# controller.net
KiCad netlist of a schematic drawn in EAGLE
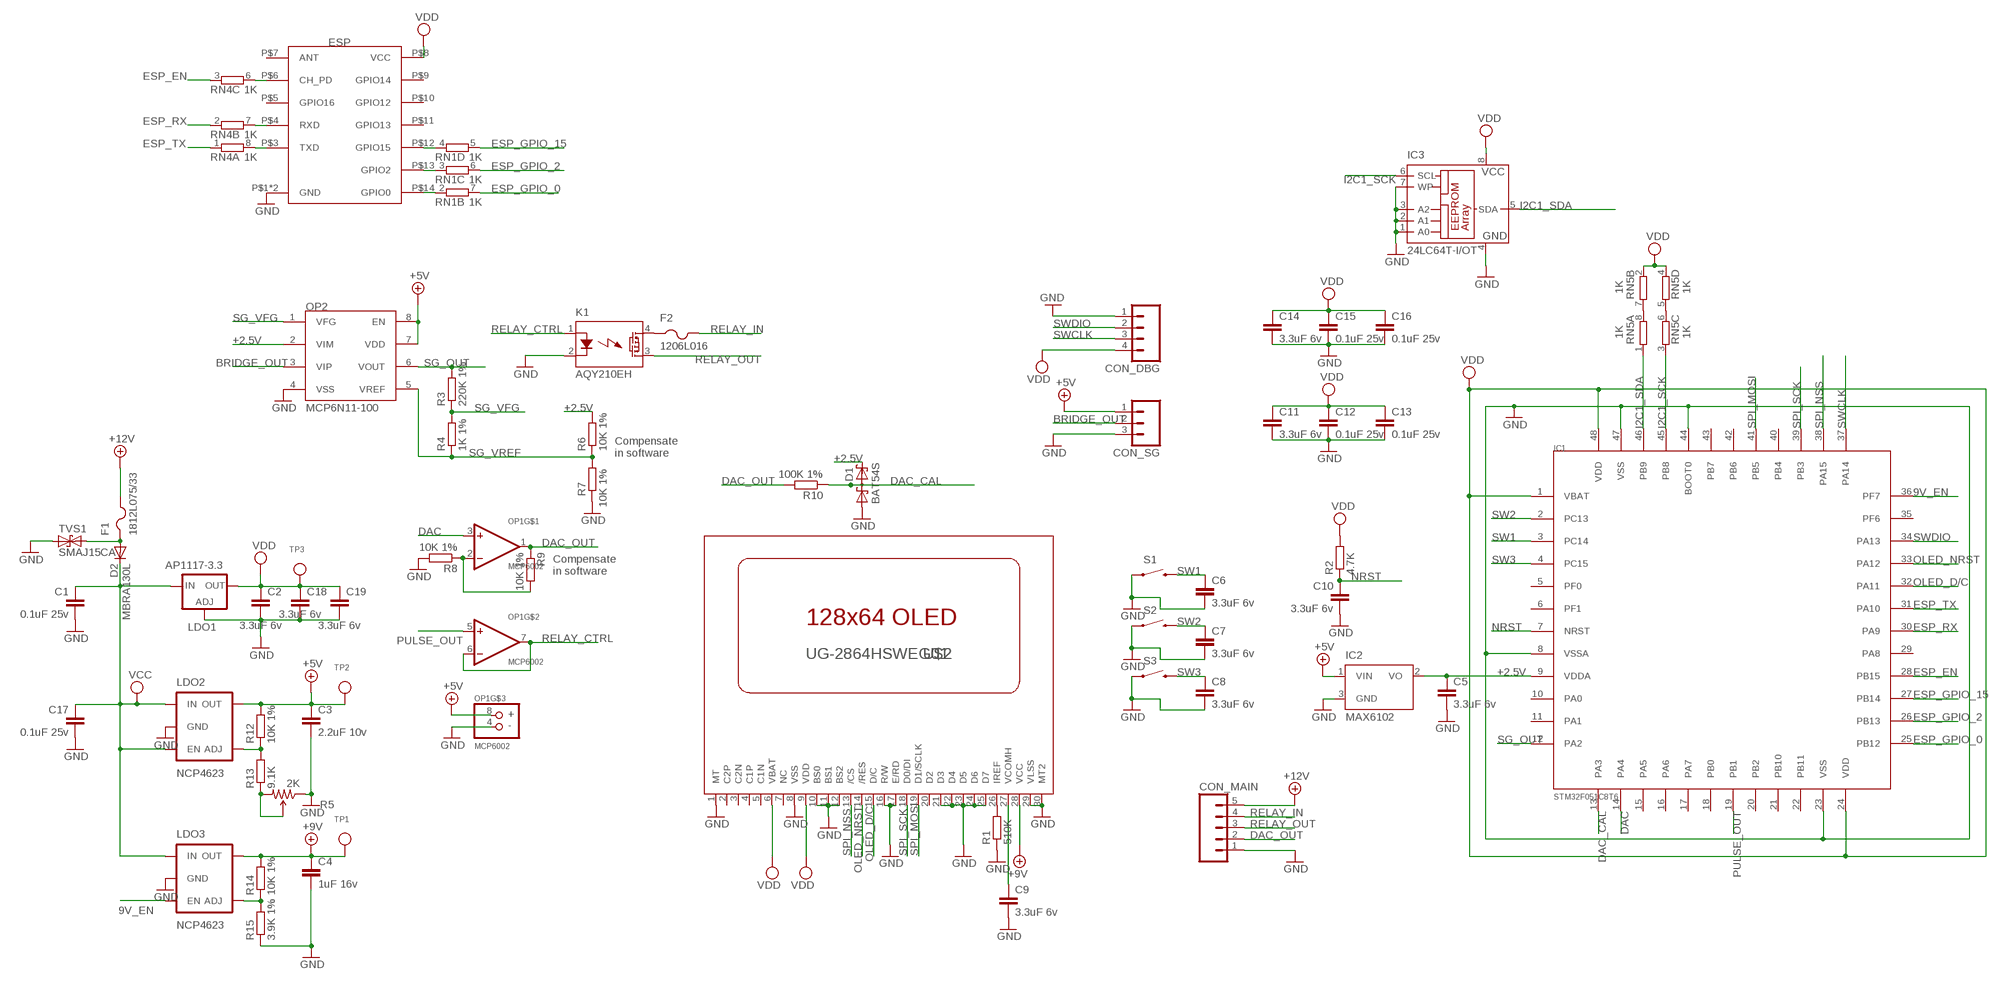
[diagram p0: schematic, sheet 1]

(export (version "E")
  (design (tool "Eeschema 10.0.6"))
  (components
    (comp (ref "C1")
      (value "0.1uF 25v")
      (footprint "eagle-import:C0603")
      (libsource (lib "eagle-import") (part "C-EUC0603"))
    )
    (comp (ref "C2")
      (value "3.3uF 6v")
      (footprint "eagle-import:C0603")
      (libsource (lib "eagle-import") (part "C-EUC0603"))
    )
    (comp (ref "C3")
      (value "2.2uF 10v")
      (footprint "eagle-import:C0603")
      (libsource (lib "eagle-import") (part "C-EUC0603"))
    )
    (comp (ref "C4")
      (value "1uF 16v")
      (footprint "eagle-import:C0603")
      (libsource (lib "eagle-import") (part "C-EUC0603"))
    )
    (comp (ref "C5")
      (value "3.3uF 6v")
      (footprint "eagle-import:C0603")
      (libsource (lib "eagle-import") (part "C-EUC0603"))
    )
    (comp (ref "C6")
      (value "3.3uF 6v")
      (footprint "eagle-import:C0603")
      (libsource (lib "eagle-import") (part "C-EUC0603"))
    )
    (comp (ref "C7")
      (value "3.3uF 6v")
      (footprint "eagle-import:C0603")
      (libsource (lib "eagle-import") (part "C-EUC0603"))
    )
    (comp (ref "C8")
      (value "3.3uF 6v")
      (footprint "eagle-import:C0603")
      (libsource (lib "eagle-import") (part "C-EUC0603"))
    )
    (comp (ref "C9")
      (value "3.3uF 6v")
      (footprint "eagle-import:C0603")
      (libsource (lib "eagle-import") (part "C-EUC0603"))
    )
    (comp (ref "C10")
      (value "3.3uF 6v")
      (footprint "eagle-import:C0603")
      (libsource (lib "eagle-import") (part "C-EUC0603"))
    )
    (comp (ref "C11")
      (value "3.3uF 6v")
      (footprint "eagle-import:C0603")
      (libsource (lib "eagle-import") (part "C-EUC0603"))
    )
    (comp (ref "C12")
      (value "0.1uF 25v")
      (footprint "eagle-import:C0603")
      (libsource (lib "eagle-import") (part "C-EUC0603"))
    )
    (comp (ref "C13")
      (value "0.1uF 25v")
      (footprint "eagle-import:C0603")
      (libsource (lib "eagle-import") (part "C-EUC0603"))
    )
    (comp (ref "C14")
      (value "3.3uF 6v")
      (footprint "eagle-import:C0603")
      (libsource (lib "eagle-import") (part "C-EUC0603"))
    )
    (comp (ref "C15")
      (value "0.1uF 25v")
      (footprint "eagle-import:C0603")
      (libsource (lib "eagle-import") (part "C-EUC0603"))
    )
    (comp (ref "C16")
      (value "0.1uF 25v")
      (footprint "eagle-import:C0603")
      (libsource (lib "eagle-import") (part "C-EUC0603"))
    )
    (comp (ref "C17")
      (value "0.1uF 25v")
      (footprint "eagle-import:C0603")
      (libsource (lib "eagle-import") (part "C-EUC0603"))
    )
    (comp (ref "C18")
      (value "3.3uF 6v")
      (footprint "eagle-import:C0603")
      (libsource (lib "eagle-import") (part "C-EUC0603"))
    )
    (comp (ref "C19")
      (value "3.3uF 6v")
      (footprint "eagle-import:C0603")
      (libsource (lib "eagle-import") (part "C-EUC0603"))
    )
    (comp (ref "CON_DBG")
      (value "M04LOCK")
      (footprint "eagle-import:1X04_LOCK")
      (libsource (lib "eagle-import") (part "M04LOCK"))
    )
    (comp (ref "CON_MAIN")
      (value "M05LOCK")
      (footprint "eagle-import:1X05_LOCK")
      (libsource (lib "eagle-import") (part "M05LOCK"))
    )
    (comp (ref "CON_SG")
      (value "M03LOCK")
      (footprint "eagle-import:1X03_LOCK")
      (libsource (lib "eagle-import") (part "M03LOCK"))
    )
    (comp (ref "D1")
      (value "BAT54S")
      (footprint "eagle-import:SOT23")
      (libsource (lib "eagle-import") (part "BAT54S"))
    )
    (comp (ref "D2")
      (value "MBRA130L")
      (footprint "eagle-import:SMA-DIODE")
      (libsource (lib "eagle-import") (part "DIODESMA"))
    )
    (comp (ref "ESP")
      (value "ESP8266")
      (footprint "eagle-import:ESP-03")
      (libsource (lib "eagle-import") (part "ESP8266"))
    )
    (comp (ref "F1")
      (value "1812L075/33")
      (footprint "eagle-import:1812")
      (libsource (lib "eagle-import") (part "PTCFUSE-1812"))
    )
    (comp (ref "F2")
      (value "1206L016")
      (footprint "eagle-import:R1206")
      (libsource (lib "eagle-import") (part "PTCFUSE-1206"))
    )
    (comp (ref "IC1")
      (value "STM32F051C8T6")
      (footprint "eagle-import:LQFP-48")
      (libsource (lib "eagle-import") (part "STM32F05XC"))
    )
    (comp (ref "IC2")
      (value "MAX6102")
      (footprint "eagle-import:SOT23")
      (libsource (lib "eagle-import") (part "MC15TT25"))
    )
    (comp (ref "IC3")
      (value "24LC64T-I/OT")
      (footprint "eagle-import:SO-08")
      (fields (field (name "MPN") "AT24C01BN-SH-B"))
      (libsource (lib "eagle-import") (part "24CSN01A"))
    )
    (comp (ref "K1")
      (value "AQY210EH")
      (footprint "eagle-import:SOP04")
      (libsource (lib "eagle-import") (part "AQYSOP21"))
    )
    (comp (ref "LDO1")
      (value "AP1117-3.3")
      (footprint "eagle-import:DPACK")
      (libsource (lib "eagle-import") (part "LD117A?DT33TR"))
    )
    (comp (ref "LDO2")
      (value "NCP4623")
      (footprint "eagle-import:SOT23-5")
      (libsource (lib "eagle-import") (part "NCP4623"))
    )
    (comp (ref "LDO3")
      (value "NCP4623")
      (footprint "eagle-import:SOT23-5")
      (libsource (lib "eagle-import") (part "NCP4623"))
    )
    (comp (ref "OP1")
      (value "MCP6002")
      (footprint "eagle-import:MSOP-8")
      (libsource (lib "eagle-import") (part "MCP6022-MSOP"))
    )
    (comp (ref "OP2")
      (value "MCP6N11-100")
      (footprint "eagle-import:SO08")
      (libsource (lib "eagle-import") (part "MCP6N11"))
    )
    (comp (ref "R1")
      (value "510K")
      (footprint "eagle-import:R0603")
      (libsource (lib "eagle-import") (part "R-EU_R0603"))
    )
    (comp (ref "R2")
      (value "4.7K")
      (footprint "eagle-import:R0603")
      (libsource (lib "eagle-import") (part "R-EU_R0603"))
    )
    (comp (ref "R3")
      (value "220K 1%")
      (footprint "eagle-import:R0603")
      (libsource (lib "eagle-import") (part "R-EU_R0603"))
    )
    (comp (ref "R4")
      (value "1K 1%")
      (footprint "eagle-import:R0603")
      (libsource (lib "eagle-import") (part "R-EU_R0603"))
    )
    (comp (ref "R5")
      (value "2K")
      (footprint "eagle-import:TRIMPOT-3MM-2")
      (libsource (lib "eagle-import") (part "TRIMPOT3MM-2"))
    )
    (comp (ref "R6")
      (value "10K 1%")
      (footprint "eagle-import:R0603")
      (libsource (lib "eagle-import") (part "R-EU_R0603"))
    )
    (comp (ref "R7")
      (value "10K 1%")
      (footprint "eagle-import:R0603")
      (libsource (lib "eagle-import") (part "R-EU_R0603"))
    )
    (comp (ref "R8")
      (value "10K 1%")
      (footprint "eagle-import:R0603")
      (libsource (lib "eagle-import") (part "R-EU_R0603"))
    )
    (comp (ref "R9")
      (value "10K 1%")
      (footprint "eagle-import:R0603")
      (libsource (lib "eagle-import") (part "R-EU_R0603"))
    )
    (comp (ref "R10")
      (value "100K 1%")
      (footprint "eagle-import:R0603")
      (libsource (lib "eagle-import") (part "R-EU_R0603"))
    )
    (comp (ref "R12")
      (value "10K 1%")
      (footprint "eagle-import:R0603")
      (libsource (lib "eagle-import") (part "R-EU_R0603"))
    )
    (comp (ref "R13")
      (value "9.1K")
      (footprint "eagle-import:R0603")
      (libsource (lib "eagle-import") (part "R-EU_R0603"))
    )
    (comp (ref "R14")
      (value "10K 1%")
      (footprint "eagle-import:R0603")
      (libsource (lib "eagle-import") (part "R-EU_R0603"))
    )
    (comp (ref "R15")
      (value "3.9K 1%")
      (footprint "eagle-import:R0603")
      (libsource (lib "eagle-import") (part "R-EU_R0603"))
    )
    (comp (ref "RN1")
      (value "1K")
      (footprint "eagle-import:CAY16")
      (libsource (lib "eagle-import") (part "4R-NCAY16"))
    )
    (comp (ref "RN4")
      (value "1K")
      (footprint "eagle-import:CAY16")
      (libsource (lib "eagle-import") (part "4R-NCAY16"))
    )
    (comp (ref "RN5")
      (value "1K")
      (footprint "eagle-import:CAY16")
      (libsource (lib "eagle-import") (part "4R-NCAY16"))
    )
    (comp (ref "S1")
      (value "SWITCH-MOMENTARY-2SMD-2")
      (footprint "eagle-import:TACTILE_SWITCH_SMD-2")
      (libsource (lib "eagle-import") (part "SWITCH-MOMENTARY-2SMD-2"))
    )
    (comp (ref "S2")
      (value "SWITCH-MOMENTARY-2SMD-2")
      (footprint "eagle-import:TACTILE_SWITCH_SMD-2")
      (libsource (lib "eagle-import") (part "SWITCH-MOMENTARY-2SMD-2"))
    )
    (comp (ref "S3")
      (value "SWITCH-MOMENTARY-2SMD-2")
      (footprint "eagle-import:TACTILE_SWITCH_SMD-2")
      (libsource (lib "eagle-import") (part "SWITCH-MOMENTARY-2SMD-2"))
    )
    (comp (ref "TP1")
      (value "TESTPOINTROUND2MM")
      (footprint "eagle-import:TESTPOINT_ROUND_2MM")
      (libsource (lib "eagle-import") (part "TESTPOINTROUND2MM"))
    )
    (comp (ref "TP2")
      (value "TESTPOINTROUND2MM")
      (footprint "eagle-import:TESTPOINT_ROUND_2MM")
      (libsource (lib "eagle-import") (part "TESTPOINTROUND2MM"))
    )
    (comp (ref "TP3")
      (value "TESTPOINTROUND2MM")
      (footprint "eagle-import:TESTPOINT_ROUND_2MM")
      (libsource (lib "eagle-import") (part "TESTPOINTROUND2MM"))
    )
    (comp (ref "TVS1")
      (value "SMAJ15CA")
      (footprint "eagle-import:SMA-DIODE")
      (libsource (lib "eagle-import") (part "TVS"))
    )
    (comp (ref "U$2")
      (value "UG-2864HSWEG01")
      (footprint "eagle-import:1X30-0.7MM")
      (libsource (lib "eagle-import") (part "UG-2864HSWEG01"))
    )
  )
  (nets
    (net (code "1") (name "+5V") (class "Default")
      (node (ref "C3") (pin "1") (pinfunction "1_1") (pintype "passive"))
      (node (ref "CON_SG") (pin "1") (pinfunction "1_1") (pintype "passive"))
      (node (ref "IC2") (pin "1") (pinfunction "VIN_1") (pintype "input"))
      (node (ref "LDO2") (pin "1") (pinfunction "OUT_1") (pintype "passive"))
      (node (ref "OP1") (pin "8") (pinfunction "+_8") (pintype "passive"))
      (node (ref "OP2") (pin "7") (pinfunction "VDD_7") (pintype "bidirectional"))
      (node (ref "OP2") (pin "8") (pinfunction "EN_8") (pintype "bidirectional"))
      (node (ref "R12") (pin "2") (pinfunction "2_2") (pintype "passive"))
      (node (ref "TP2") (pin "P$1") (pinfunction "P$1_P$1") (pintype "bidirectional"))
    )
    (net (code "2") (name "+9V") (class "Default")
      (node (ref "C4") (pin "1") (pinfunction "1_1") (pintype "passive"))
      (node (ref "LDO3") (pin "1") (pinfunction "OUT_1") (pintype "passive"))
      (node (ref "R14") (pin "2") (pinfunction "2_2") (pintype "passive"))
      (node (ref "TP1") (pin "P$1") (pinfunction "P$1_P$1") (pintype "bidirectional"))
      (node (ref "U$2") (pin "28") (pinfunction "VCC_28") (pintype "power_in"))
    )
    (net (code "3") (name "+12V") (class "Default")
      (node (ref "CON_MAIN") (pin "5") (pinfunction "5_5") (pintype "passive"))
      (node (ref "F1") (pin "2") (pinfunction "2_2") (pintype "passive"))
    )
    (net (code "4") (name "/+2.5V") (class "Default")
      (node (ref "C5") (pin "1") (pinfunction "1_1") (pintype "passive"))
      (node (ref "D1") (pin "2") (pinfunction "C2_2") (pintype "passive"))
      (node (ref "IC1") (pin "9") (pinfunction "VDDA_9") (pintype "bidirectional"))
      (node (ref "IC2") (pin "2") (pinfunction "VO_2") (pintype "output"))
      (node (ref "OP2") (pin "2") (pinfunction "VIM_2") (pintype "bidirectional"))
      (node (ref "R6") (pin "2") (pinfunction "2_2") (pintype "passive"))
    )
    (net (code "5") (name "/9V_EN") (class "Default")
      (node (ref "IC1") (pin "36") (pinfunction "PF7_36") (pintype "bidirectional"))
      (node (ref "LDO3") (pin "5") (pinfunction "EN_5") (pintype "input"))
    )
    (net (code "6") (name "/BRIDGE_OUT") (class "Default")
      (node (ref "CON_SG") (pin "2") (pinfunction "2_2") (pintype "passive"))
      (node (ref "OP2") (pin "3") (pinfunction "VIP_3") (pintype "bidirectional"))
    )
    (net (code "7") (name "/DAC") (class "Default")
      (node (ref "IC1") (pin "14") (pinfunction "PA4_14") (pintype "bidirectional"))
      (node (ref "OP1") (pin "3") (pinfunction "+IN_3") (pintype "input"))
    )
    (net (code "8") (name "/DAC_CAL") (class "Default")
      (node (ref "D1") (pin "3") (pinfunction "C1A2_3") (pintype "passive"))
      (node (ref "IC1") (pin "13") (pinfunction "PA3_13") (pintype "bidirectional"))
      (node (ref "R10") (pin "1") (pinfunction "1_1") (pintype "passive"))
    )
    (net (code "9") (name "/DAC_OUT") (class "Default")
      (node (ref "CON_MAIN") (pin "2") (pinfunction "2_2") (pintype "passive"))
      (node (ref "OP1") (pin "1") (pinfunction "OUT_1") (pintype "output"))
      (node (ref "R10") (pin "2") (pinfunction "2_2") (pintype "passive"))
      (node (ref "R9") (pin "1") (pinfunction "1_1") (pintype "passive"))
    )
    (net (code "10") (name "/ESP_EN") (class "Default")
      (node (ref "IC1") (pin "28") (pinfunction "PB15_28") (pintype "bidirectional"))
      (node (ref "RN4") (pin "3") (pinfunction "1_3") (pintype "passive"))
    )
    (net (code "11") (name "/ESP_GPIO_0") (class "Default")
      (node (ref "IC1") (pin "25") (pinfunction "PB12_25") (pintype "bidirectional"))
      (node (ref "RN1") (pin "7") (pinfunction "2_7") (pintype "passive"))
    )
    (net (code "12") (name "/ESP_GPIO_2") (class "Default")
      (node (ref "IC1") (pin "26") (pinfunction "PB13_26") (pintype "bidirectional"))
      (node (ref "RN1") (pin "6") (pinfunction "2_6") (pintype "passive"))
    )
    (net (code "13") (name "/ESP_GPIO_15") (class "Default")
      (node (ref "IC1") (pin "27") (pinfunction "PB14_27") (pintype "bidirectional"))
      (node (ref "RN1") (pin "5") (pinfunction "2_5") (pintype "passive"))
    )
    (net (code "14") (name "/ESP_RX") (class "Default")
      (node (ref "IC1") (pin "30") (pinfunction "PA9_30") (pintype "bidirectional"))
      (node (ref "RN4") (pin "2") (pinfunction "1_2") (pintype "passive"))
    )
    (net (code "15") (name "/ESP_TX") (class "Default")
      (node (ref "IC1") (pin "31") (pinfunction "PA10_31") (pintype "bidirectional"))
      (node (ref "RN4") (pin "1") (pinfunction "1_1") (pintype "passive"))
    )
    (net (code "16") (name "/I2C1_SCK") (class "Default")
      (node (ref "IC1") (pin "45") (pinfunction "PB8_45") (pintype "bidirectional"))
      (node (ref "IC3") (pin "6") (pinfunction "SCL_6") (pintype "input"))
      (node (ref "RN5") (pin "3") (pinfunction "1_3") (pintype "passive"))
    )
    (net (code "17") (name "/I2C1_SDA") (class "Default")
      (node (ref "IC1") (pin "46") (pinfunction "PB9_46") (pintype "bidirectional"))
      (node (ref "IC3") (pin "5") (pinfunction "SDA_5") (pintype "bidirectional"))
      (node (ref "RN5") (pin "1") (pinfunction "1_1") (pintype "passive"))
    )
    (net (code "18") (name "/NRST") (class "Default")
      (node (ref "C10") (pin "1") (pinfunction "1_1") (pintype "passive"))
      (node (ref "IC1") (pin "7") (pinfunction "NRST_7") (pintype "bidirectional"))
      (node (ref "R2") (pin "1") (pinfunction "1_1") (pintype "passive"))
    )
    (net (code "19") (name "/OLED_D{slash}C") (class "Default")
      (node (ref "IC1") (pin "32") (pinfunction "PA11_32") (pintype "bidirectional"))
      (node (ref "U$2") (pin "15") (pinfunction "D/C_15") (pintype "input"))
    )
    (net (code "20") (name "/OLED_NRST") (class "Default")
      (node (ref "IC1") (pin "33") (pinfunction "PA12_33") (pintype "bidirectional"))
      (node (ref "U$2") (pin "14") (pinfunction "/RES_14") (pintype "input"))
    )
    (net (code "21") (name "/PULSE_OUT") (class "Default")
      (node (ref "IC1") (pin "19") (pinfunction "PB1_19") (pintype "bidirectional"))
      (node (ref "OP1") (pin "5") (pinfunction "+IN_5") (pintype "input"))
    )
    (net (code "22") (name "/RELAY_CTRL") (class "Default")
      (node (ref "K1") (pin "1") (pinfunction "A_1") (pintype "passive"))
      (node (ref "OP1") (pin "6") (pinfunction "-IN_6") (pintype "input"))
      (node (ref "OP1") (pin "7") (pinfunction "OUT_7") (pintype "output"))
    )
    (net (code "23") (name "/RELAY_IN") (class "Default")
      (node (ref "CON_MAIN") (pin "4") (pinfunction "4_4") (pintype "passive"))
      (node (ref "F2") (pin "2") (pinfunction "2_2") (pintype "passive"))
    )
    (net (code "24") (name "/RELAY_OUT") (class "Default")
      (node (ref "CON_MAIN") (pin "3") (pinfunction "3_3") (pintype "passive"))
      (node (ref "K1") (pin "3") (pinfunction "DS2_3") (pintype "passive"))
    )
    (net (code "25") (name "/SG_OUT") (class "Default")
      (node (ref "IC1") (pin "12") (pinfunction "PA2_12") (pintype "bidirectional"))
      (node (ref "OP2") (pin "6") (pinfunction "VOUT_6") (pintype "bidirectional"))
      (node (ref "R3") (pin "2") (pinfunction "2_2") (pintype "passive"))
    )
    (net (code "26") (name "/SG_VFG") (class "Default")
      (node (ref "OP2") (pin "1") (pinfunction "VFG_1") (pintype "bidirectional"))
      (node (ref "R3") (pin "1") (pinfunction "1_1") (pintype "passive"))
      (node (ref "R4") (pin "2") (pinfunction "2_2") (pintype "passive"))
    )
    (net (code "27") (name "/SG_VREF") (class "Default")
      (node (ref "OP2") (pin "5") (pinfunction "VREF_5") (pintype "bidirectional"))
      (node (ref "R4") (pin "1") (pinfunction "1_1") (pintype "passive"))
      (node (ref "R6") (pin "1") (pinfunction "1_1") (pintype "passive"))
      (node (ref "R7") (pin "2") (pinfunction "2_2") (pintype "passive"))
    )
    (net (code "28") (name "/SPI_MOSI") (class "Default")
      (node (ref "IC1") (pin "41") (pinfunction "PB5_41") (pintype "bidirectional"))
      (node (ref "U$2") (pin "19") (pinfunction "D1/SCLK_19") (pintype "bidirectional"))
    )
    (net (code "29") (name "/SPI_NSS") (class "Default")
      (node (ref "IC1") (pin "38") (pinfunction "PA15_38") (pintype "bidirectional"))
      (node (ref "U$2") (pin "13") (pinfunction "/CS_13") (pintype "input"))
    )
    (net (code "30") (name "/SPI_SCK") (class "Default")
      (node (ref "IC1") (pin "39") (pinfunction "PB3_39") (pintype "bidirectional"))
      (node (ref "U$2") (pin "18") (pinfunction "D0/DI_18") (pintype "bidirectional"))
    )
    (net (code "31") (name "/SW1") (class "Default")
      (node (ref "C6") (pin "1") (pinfunction "1_1") (pintype "passive"))
      (node (ref "IC1") (pin "3") (pinfunction "PC14_3") (pintype "bidirectional"))
      (node (ref "S1") (pin "1") (pinfunction "2_1") (pintype "passive"))
    )
    (net (code "32") (name "/SW2") (class "Default")
      (node (ref "C7") (pin "1") (pinfunction "1_1") (pintype "passive"))
      (node (ref "IC1") (pin "2") (pinfunction "PC13_2") (pintype "bidirectional"))
      (node (ref "S2") (pin "1") (pinfunction "2_1") (pintype "passive"))
    )
    (net (code "33") (name "/SW3") (class "Default")
      (node (ref "C8") (pin "1") (pinfunction "1_1") (pintype "passive"))
      (node (ref "IC1") (pin "4") (pinfunction "PC15_4") (pintype "bidirectional"))
      (node (ref "S3") (pin "1") (pinfunction "2_1") (pintype "passive"))
    )
    (net (code "34") (name "/SWCLK") (class "Default")
      (node (ref "CON_DBG") (pin "3") (pinfunction "3_3") (pintype "passive"))
      (node (ref "IC1") (pin "37") (pinfunction "PA14_37") (pintype "bidirectional"))
    )
    (net (code "35") (name "/SWDIO") (class "Default")
      (node (ref "CON_DBG") (pin "2") (pinfunction "2_2") (pintype "passive"))
      (node (ref "IC1") (pin "34") (pinfunction "PA13_34") (pintype "bidirectional"))
    )
    (net (code "36") (name "GND") (class "Default")
      (node (ref "C1") (pin "2") (pinfunction "2_2") (pintype "passive"))
      (node (ref "C10") (pin "2") (pinfunction "2_2") (pintype "passive"))
      (node (ref "C11") (pin "2") (pinfunction "2_2") (pintype "passive"))
      (node (ref "C12") (pin "2") (pinfunction "2_2") (pintype "passive"))
      (node (ref "C13") (pin "2") (pinfunction "2_2") (pintype "passive"))
      (node (ref "C14") (pin "2") (pinfunction "2_2") (pintype "passive"))
      (node (ref "C15") (pin "2") (pinfunction "2_2") (pintype "passive"))
      (node (ref "C16") (pin "2") (pinfunction "2_2") (pintype "passive"))
      (node (ref "C17") (pin "2") (pinfunction "2_2") (pintype "passive"))
      (node (ref "C18") (pin "2") (pinfunction "2_2") (pintype "passive"))
      (node (ref "C19") (pin "2") (pinfunction "2_2") (pintype "passive"))
      (node (ref "C2") (pin "2") (pinfunction "2_2") (pintype "passive"))
      (node (ref "C3") (pin "2") (pinfunction "2_2") (pintype "passive"))
      (node (ref "C4") (pin "2") (pinfunction "2_2") (pintype "passive"))
      (node (ref "C5") (pin "2") (pinfunction "2_2") (pintype "passive"))
      (node (ref "C6") (pin "2") (pinfunction "2_2") (pintype "passive"))
      (node (ref "C7") (pin "2") (pinfunction "2_2") (pintype "passive"))
      (node (ref "C8") (pin "2") (pinfunction "2_2") (pintype "passive"))
      (node (ref "C9") (pin "2") (pinfunction "2_2") (pintype "passive"))
      (node (ref "CON_DBG") (pin "1") (pinfunction "1_1") (pintype "passive"))
      (node (ref "CON_MAIN") (pin "1") (pinfunction "1_1") (pintype "passive"))
      (node (ref "CON_SG") (pin "3") (pinfunction "3_3") (pintype "passive"))
      (node (ref "D1") (pin "1") (pinfunction "A1_1") (pintype "passive"))
      (node (ref "ESP") (pin "P$1") (pinfunction "GND_P$1") (pintype "bidirectional"))
      (node (ref "ESP") (pin "P$2") (pinfunction "GND_P$2") (pintype "bidirectional"))
      (node (ref "IC1") (pin "23") (pinfunction "VSS_23") (pintype "bidirectional"))
      (node (ref "IC1") (pin "44") (pinfunction "BOOT0_44") (pintype "bidirectional"))
      (node (ref "IC1") (pin "47") (pinfunction "VSS_47") (pintype "bidirectional"))
      (node (ref "IC1") (pin "8") (pinfunction "VSSA_8") (pintype "bidirectional"))
      (node (ref "IC2") (pin "3") (pinfunction "GND_3") (pintype "passive"))
      (node (ref "IC3") (pin "1") (pinfunction "A0_1") (pintype "input"))
      (node (ref "IC3") (pin "2") (pinfunction "A1_2") (pintype "input"))
      (node (ref "IC3") (pin "3") (pinfunction "A2_3") (pintype "input"))
      (node (ref "IC3") (pin "4") (pinfunction "GND_4") (pintype "power_in"))
      (node (ref "IC3") (pin "7") (pinfunction "WP_7") (pintype "input"))
      (node (ref "K1") (pin "2") (pinfunction "K_2") (pintype "passive"))
      (node (ref "LDO1") (pin "1") (pinfunction "ADJ_1") (pintype "input"))
      (node (ref "LDO2") (pin "2") (pinfunction "GND_2") (pintype "input"))
      (node (ref "LDO3") (pin "2") (pinfunction "GND_2") (pintype "input"))
      (node (ref "OP1") (pin "4") (pinfunction "-_4") (pintype "passive"))
      (node (ref "OP2") (pin "4") (pinfunction "VSS_4") (pintype "bidirectional"))
      (node (ref "R1") (pin "1") (pinfunction "1_1") (pintype "passive"))
      (node (ref "R15") (pin "1") (pinfunction "1_1") (pintype "passive"))
      (node (ref "R5") (pin "1") (pinfunction "CCW_1") (pintype "passive"))
      (node (ref "R7") (pin "1") (pinfunction "1_1") (pintype "passive"))
      (node (ref "R8") (pin "2") (pinfunction "2_2") (pintype "passive"))
      (node (ref "S1") (pin "2") (pinfunction "1_2") (pintype "passive"))
      (node (ref "S2") (pin "2") (pinfunction "1_2") (pintype "passive"))
      (node (ref "S3") (pin "2") (pinfunction "1_2") (pintype "passive"))
      (node (ref "TVS1") (pin "A") (pinfunction "1_A") (pintype "passive"))
      (node (ref "U$2") (pin "1") (pinfunction "MT_1") (pintype "input"))
      (node (ref "U$2") (pin "10") (pinfunction "BS0_10") (pintype "input"))
      (node (ref "U$2") (pin "11") (pinfunction "BS1_11") (pintype "input"))
      (node (ref "U$2") (pin "12") (pinfunction "BS2_12") (pintype "input"))
      (node (ref "U$2") (pin "16") (pinfunction "R/W_16") (pintype "input"))
      (node (ref "U$2") (pin "17") (pinfunction "E/RD_17") (pintype "input"))
      (node (ref "U$2") (pin "21") (pinfunction "D3_21") (pintype "bidirectional"))
      (node (ref "U$2") (pin "22") (pinfunction "D4_22") (pintype "bidirectional"))
      (node (ref "U$2") (pin "23") (pinfunction "D5_23") (pintype "bidirectional"))
      (node (ref "U$2") (pin "24") (pinfunction "D6_24") (pintype "bidirectional"))
      (node (ref "U$2") (pin "25") (pinfunction "D7_25") (pintype "bidirectional"))
      (node (ref "U$2") (pin "29") (pinfunction "VLSS_29") (pintype "power_in"))
      (node (ref "U$2") (pin "30") (pinfunction "MT2_30") (pintype "input"))
      (node (ref "U$2") (pin "8") (pinfunction "VSS_8") (pintype "power_in"))
    )
    (net (code "37") (name "Net-(ESP-CH_PD)") (class "Default")
      (node (ref "ESP") (pin "P$6") (pinfunction "CH_PD_P$6") (pintype "bidirectional"))
      (node (ref "RN4") (pin "6") (pinfunction "2_6") (pintype "passive"))
    )
    (net (code "38") (name "Net-(ESP-GPIO0)") (class "Default")
      (node (ref "ESP") (pin "P$14") (pinfunction "GPIO0_P$14") (pintype "bidirectional"))
      (node (ref "RN1") (pin "2") (pinfunction "1_2") (pintype "passive"))
    )
    (net (code "39") (name "Net-(ESP-GPIO2)") (class "Default")
      (node (ref "ESP") (pin "P$13") (pinfunction "GPIO2_P$13") (pintype "bidirectional"))
      (node (ref "RN1") (pin "3") (pinfunction "1_3") (pintype "passive"))
    )
    (net (code "40") (name "Net-(ESP-GPIO15)") (class "Default")
      (node (ref "ESP") (pin "P$12") (pinfunction "GPIO15_P$12") (pintype "bidirectional"))
      (node (ref "RN1") (pin "4") (pinfunction "1_4") (pintype "passive"))
    )
    (net (code "41") (name "Net-(ESP-RXD)") (class "Default")
      (node (ref "ESP") (pin "P$4") (pinfunction "RXD_P$4") (pintype "bidirectional"))
      (node (ref "RN4") (pin "7") (pinfunction "2_7") (pintype "passive"))
    )
    (net (code "42") (name "Net-(ESP-TXD)") (class "Default")
      (node (ref "ESP") (pin "P$3") (pinfunction "TXD_P$3") (pintype "bidirectional"))
      (node (ref "RN4") (pin "8") (pinfunction "2_8") (pintype "passive"))
    )
    (net (code "43") (name "Net-(K1-DS1)") (class "Default")
      (node (ref "F2") (pin "1") (pinfunction "1_1") (pintype "passive"))
      (node (ref "K1") (pin "4") (pinfunction "DS1_4") (pintype "passive"))
    )
    (net (code "44") (name "Net-(LDO2-ADJ)") (class "Default")
      (node (ref "LDO2") (pin "4") (pinfunction "ADJ_4") (pintype "input"))
      (node (ref "R12") (pin "1") (pinfunction "1_1") (pintype "passive"))
      (node (ref "R13") (pin "2") (pinfunction "2_2") (pintype "passive"))
    )
    (net (code "45") (name "Net-(LDO3-ADJ)") (class "Default")
      (node (ref "LDO3") (pin "4") (pinfunction "ADJ_4") (pintype "input"))
      (node (ref "R14") (pin "1") (pinfunction "1_1") (pintype "passive"))
      (node (ref "R15") (pin "2") (pinfunction "2_2") (pintype "passive"))
    )
    (net (code "46") (name "Net-(OP1A--IN)") (class "Default")
      (node (ref "OP1") (pin "2") (pinfunction "-IN_2") (pintype "input"))
      (node (ref "R8") (pin "1") (pinfunction "1_1") (pintype "passive"))
      (node (ref "R9") (pin "2") (pinfunction "2_2") (pintype "passive"))
    )
    (net (code "47") (name "Net-(R5-CW)") (class "Default")
      (node (ref "R13") (pin "1") (pinfunction "1_1") (pintype "passive"))
      (node (ref "R5") (pin "2") (pinfunction "WIPER_2") (pintype "passive"))
      (node (ref "R5") (pin "3") (pinfunction "CW_3") (pintype "passive"))
    )
    (net (code "48") (name "Net-(RN5A-2)") (class "Default")
      (node (ref "RN5") (pin "7") (pinfunction "2_7") (pintype "passive"))
      (node (ref "RN5") (pin "8") (pinfunction "2_8") (pintype "passive"))
    )
    (net (code "49") (name "Net-(RN5C-2)") (class "Default")
      (node (ref "RN5") (pin "5") (pinfunction "2_5") (pintype "passive"))
      (node (ref "RN5") (pin "6") (pinfunction "2_6") (pintype "passive"))
    )
    (net (code "50") (name "Net-(TVS1-2)") (class "Default")
      (node (ref "D2") (pin "A") (pinfunction "A_A") (pintype "passive"))
      (node (ref "F1") (pin "1") (pinfunction "1_1") (pintype "passive"))
      (node (ref "TVS1") (pin "C") (pinfunction "2_C") (pintype "passive"))
    )
    (net (code "51") (name "Net-(U$2-IREF)") (class "Default")
      (node (ref "R1") (pin "2") (pinfunction "2_2") (pintype "passive"))
      (node (ref "U$2") (pin "26") (pinfunction "IREF_26") (pintype "input"))
    )
    (net (code "52") (name "Net-(U$2-VCOMH)") (class "Default")
      (node (ref "C9") (pin "1") (pinfunction "1_1") (pintype "passive"))
      (node (ref "U$2") (pin "27") (pinfunction "VCOMH_27") (pintype "output"))
    )
    (net (code "53") (name "VCC") (class "Default")
      (node (ref "C1") (pin "1") (pinfunction "1_1") (pintype "passive"))
      (node (ref "C17") (pin "1") (pinfunction "1_1") (pintype "passive"))
      (node (ref "D2") (pin "C") (pinfunction "C_C") (pintype "passive"))
      (node (ref "LDO1") (pin "3") (pinfunction "IN_3") (pintype "input"))
      (node (ref "LDO2") (pin "3") (pinfunction "IN_3") (pintype "input"))
      (node (ref "LDO2") (pin "5") (pinfunction "EN_5") (pintype "input"))
      (node (ref "LDO3") (pin "3") (pinfunction "IN_3") (pintype "input"))
    )
    (net (code "54") (name "VDD") (class "Default")
      (node (ref "C11") (pin "1") (pinfunction "1_1") (pintype "passive"))
      (node (ref "C12") (pin "1") (pinfunction "1_1") (pintype "passive"))
      (node (ref "C13") (pin "1") (pinfunction "1_1") (pintype "passive"))
      (node (ref "C14") (pin "1") (pinfunction "1_1") (pintype "passive"))
      (node (ref "C15") (pin "1") (pinfunction "1_1") (pintype "passive"))
      (node (ref "C16") (pin "1") (pinfunction "1_1") (pintype "passive"))
      (node (ref "C18") (pin "1") (pinfunction "1_1") (pintype "passive"))
      (node (ref "C19") (pin "1") (pinfunction "1_1") (pintype "passive"))
      (node (ref "C2") (pin "1") (pinfunction "1_1") (pintype "passive"))
      (node (ref "CON_DBG") (pin "4") (pinfunction "4_4") (pintype "passive"))
      (node (ref "ESP") (pin "P$8") (pinfunction "VCC_P$8") (pintype "bidirectional"))
      (node (ref "IC1") (pin "1") (pinfunction "VBAT_1") (pintype "bidirectional"))
      (node (ref "IC1") (pin "24") (pinfunction "VDD_24") (pintype "bidirectional"))
      (node (ref "IC1") (pin "48") (pinfunction "VDD_48") (pintype "bidirectional"))
      (node (ref "IC3") (pin "8") (pinfunction "VCC_8") (pintype "power_in"))
      (node (ref "LDO1") (pin "4") (pinfunction "OUT_4") (pintype "passive"))
      (node (ref "R2") (pin "2") (pinfunction "2_2") (pintype "passive"))
      (node (ref "RN5") (pin "2") (pinfunction "1_2") (pintype "passive"))
      (node (ref "RN5") (pin "4") (pinfunction "1_4") (pintype "passive"))
      (node (ref "TP3") (pin "P$1") (pinfunction "P$1_P$1") (pintype "bidirectional"))
      (node (ref "U$2") (pin "6") (pinfunction "VBAT_6") (pintype "input"))
      (node (ref "U$2") (pin "9") (pinfunction "VDD_9") (pintype "power_in"))
    )
    (net (code "55") (name "unconnected-(ESP-ANT-PadP$7)") (class "Default")
      (node (ref "ESP") (pin "P$7") (pinfunction "ANT_P$7") (pintype "bidirectional"))
    )
    (net (code "56") (name "unconnected-(ESP-GPIO12-PadP$10)") (class "Default")
      (node (ref "ESP") (pin "P$10") (pinfunction "GPIO12_P$10") (pintype "bidirectional"))
    )
    (net (code "57") (name "unconnected-(ESP-GPIO13-PadP$11)") (class "Default")
      (node (ref "ESP") (pin "P$11") (pinfunction "GPIO13_P$11") (pintype "bidirectional"))
    )
    (net (code "58") (name "unconnected-(ESP-GPIO14-PadP$9)") (class "Default")
      (node (ref "ESP") (pin "P$9") (pinfunction "GPIO14_P$9") (pintype "bidirectional"))
    )
    (net (code "59") (name "unconnected-(ESP-GPIO16-PadP$5)") (class "Default")
      (node (ref "ESP") (pin "P$5") (pinfunction "GPIO16_P$5") (pintype "bidirectional"))
    )
    (net (code "60") (name "unconnected-(IC1-PA0-Pad10)") (class "Default")
      (node (ref "IC1") (pin "10") (pinfunction "PA0_10") (pintype "bidirectional"))
    )
    (net (code "61") (name "unconnected-(IC1-PA1-Pad11)") (class "Default")
      (node (ref "IC1") (pin "11") (pinfunction "PA1_11") (pintype "bidirectional"))
    )
    (net (code "62") (name "unconnected-(IC1-PA5-Pad15)") (class "Default")
      (node (ref "IC1") (pin "15") (pinfunction "PA5_15") (pintype "bidirectional"))
    )
    (net (code "63") (name "unconnected-(IC1-PA6-Pad16)") (class "Default")
      (node (ref "IC1") (pin "16") (pinfunction "PA6_16") (pintype "bidirectional"))
    )
    (net (code "64") (name "unconnected-(IC1-PA7-Pad17)") (class "Default")
      (node (ref "IC1") (pin "17") (pinfunction "PA7_17") (pintype "bidirectional"))
    )
    (net (code "65") (name "unconnected-(IC1-PA8-Pad29)") (class "Default")
      (node (ref "IC1") (pin "29") (pinfunction "PA8_29") (pintype "bidirectional"))
    )
    (net (code "66") (name "unconnected-(IC1-PB0-Pad18)") (class "Default")
      (node (ref "IC1") (pin "18") (pinfunction "PB0_18") (pintype "bidirectional"))
    )
    (net (code "67") (name "unconnected-(IC1-PB2-Pad20)") (class "Default")
      (node (ref "IC1") (pin "20") (pinfunction "PB2_20") (pintype "bidirectional"))
    )
    (net (code "68") (name "unconnected-(IC1-PB4-Pad40)") (class "Default")
      (node (ref "IC1") (pin "40") (pinfunction "PB4_40") (pintype "bidirectional"))
    )
    (net (code "69") (name "unconnected-(IC1-PB6-Pad42)") (class "Default")
      (node (ref "IC1") (pin "42") (pinfunction "PB6_42") (pintype "bidirectional"))
    )
    (net (code "70") (name "unconnected-(IC1-PB7-Pad43)") (class "Default")
      (node (ref "IC1") (pin "43") (pinfunction "PB7_43") (pintype "bidirectional"))
    )
    (net (code "71") (name "unconnected-(IC1-PB10-Pad21)") (class "Default")
      (node (ref "IC1") (pin "21") (pinfunction "PB10_21") (pintype "bidirectional"))
    )
    (net (code "72") (name "unconnected-(IC1-PB11-Pad22)") (class "Default")
      (node (ref "IC1") (pin "22") (pinfunction "PB11_22") (pintype "bidirectional"))
    )
    (net (code "73") (name "unconnected-(IC1-PF0-Pad5)") (class "Default")
      (node (ref "IC1") (pin "5") (pinfunction "PF0_5") (pintype "bidirectional"))
    )
    (net (code "74") (name "unconnected-(IC1-PF1-Pad6)") (class "Default")
      (node (ref "IC1") (pin "6") (pinfunction "PF1_6") (pintype "bidirectional"))
    )
    (net (code "75") (name "unconnected-(IC1-PF6-Pad35)") (class "Default")
      (node (ref "IC1") (pin "35") (pinfunction "PF6_35") (pintype "bidirectional"))
    )
    (net (code "76") (name "unconnected-(U$2-C1N-Pad5)") (class "Default")
      (node (ref "U$2") (pin "5") (pinfunction "C1N_5") (pintype "input"))
    )
    (net (code "77") (name "unconnected-(U$2-C1P-Pad4)") (class "Default")
      (node (ref "U$2") (pin "4") (pinfunction "C1P_4") (pintype "input"))
    )
    (net (code "78") (name "unconnected-(U$2-C2N-Pad3)") (class "Default")
      (node (ref "U$2") (pin "3") (pinfunction "C2N_3") (pintype "input"))
    )
    (net (code "79") (name "unconnected-(U$2-C2P-Pad2)") (class "Default")
      (node (ref "U$2") (pin "2") (pinfunction "C2P_2") (pintype "input"))
    )
    (net (code "80") (name "unconnected-(U$2-D2-Pad20)") (class "Default")
      (node (ref "U$2") (pin "20") (pinfunction "D2_20") (pintype "bidirectional"))
    )
    (net (code "81") (name "unconnected-(U$2-NC-Pad7)") (class "Default")
      (node (ref "U$2") (pin "7") (pinfunction "NC_7") (pintype "no_connect"))
    )
  )
)
